# ardufocus.net
KiCad netlist of a schematic drawn in EAGLE
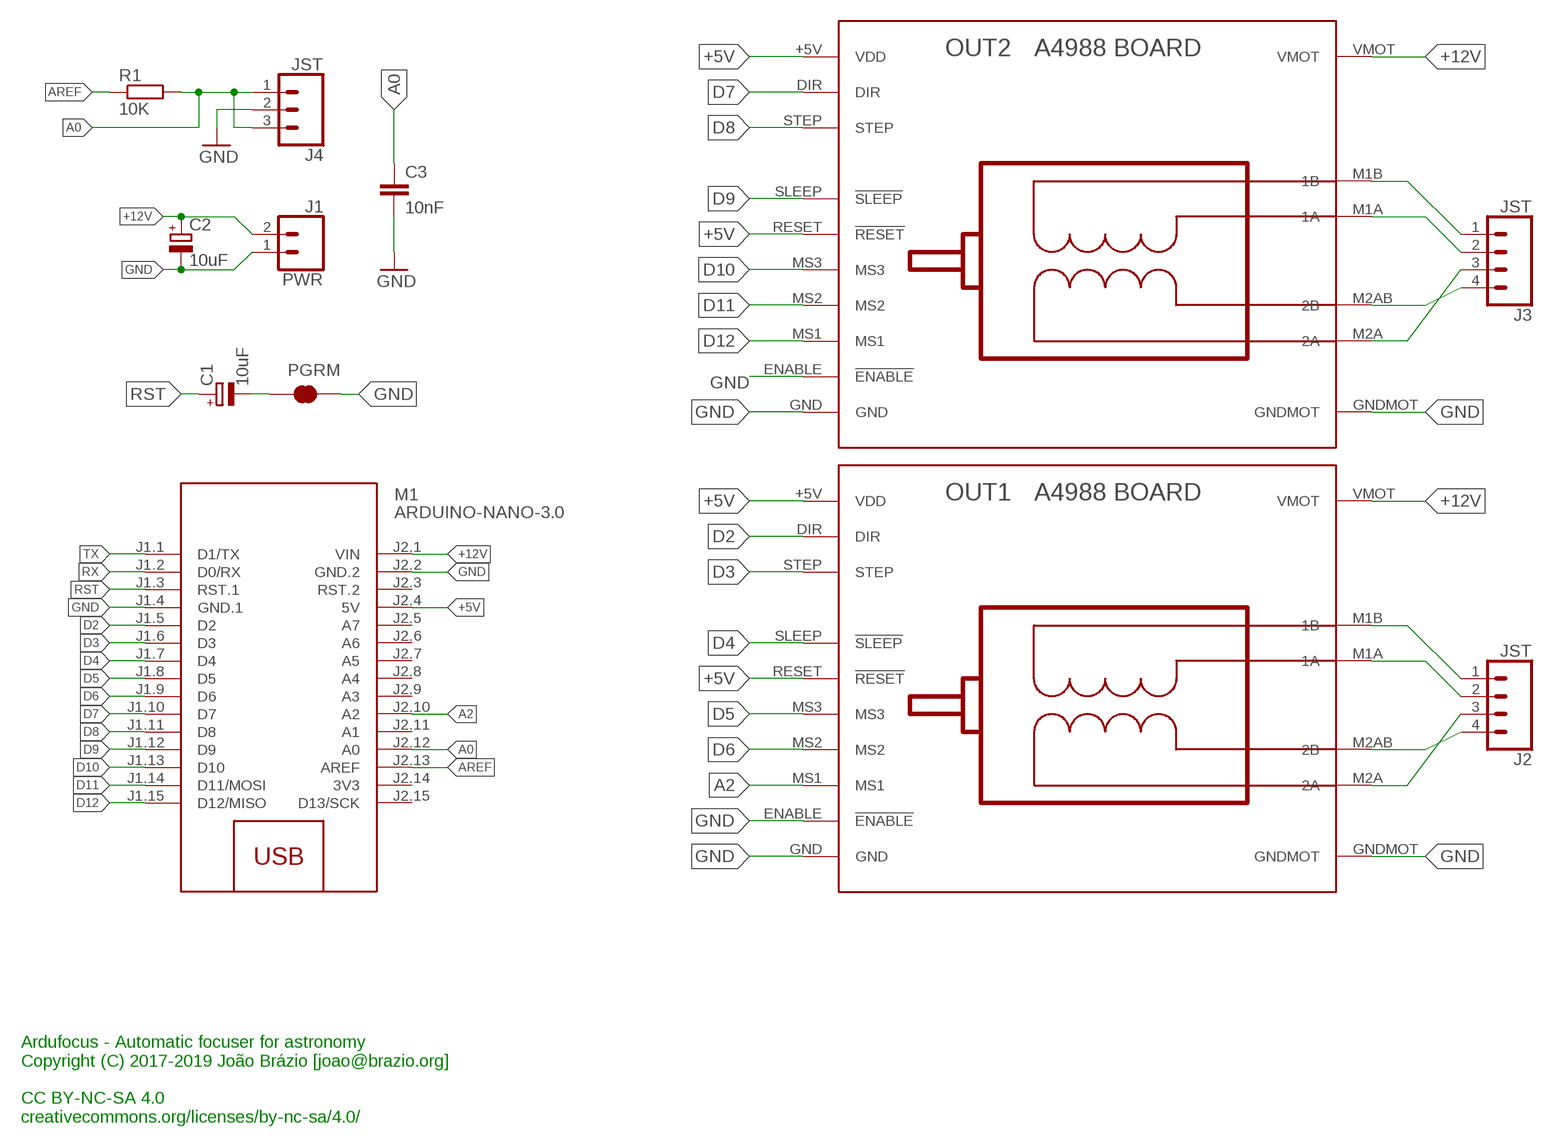
[diagram p0: schematic, sheet 1]

(export (version "E")
  (design (tool "Eeschema 10.0.6"))
  (components
    (comp (ref "C1")
      (value "10uF")
      (footprint "eagle-import:E1,8-4")
      (libsource (lib "eagle-import") (part "CPOL-EUE1.8-4"))
    )
    (comp (ref "C2")
      (value "10uF")
      (footprint "eagle-import:E2,5-6E")
      (libsource (lib "eagle-import") (part "CPOL-EUE2,5-6E"))
    )
    (comp (ref "C3")
      (value "10nF")
      (footprint "eagle-import:C3216")
      (libsource (lib "eagle-import") (part "C-EUC3216"))
    )
    (comp (ref "J1")
      (value "PWR")
      (footprint "eagle-import:SCREWTERMINAL-5MM-2")
      (libsource (lib "eagle-import") (part "CONN_025MM"))
    )
    (comp (ref "J2")
      (value "JST")
      (footprint "eagle-import:JST-4-PTH-VERT")
      (libsource (lib "eagle-import") (part "CONN_04JST-PTH-VERT"))
    )
    (comp (ref "J3")
      (value "JST")
      (footprint "eagle-import:JST-4-PTH-VERT")
      (libsource (lib "eagle-import") (part "CONN_04JST-PTH-VERT"))
    )
    (comp (ref "J4")
      (value "JST")
      (footprint "eagle-import:JST-3-PTH-VERT")
      (libsource (lib "eagle-import") (part "CONN_03JST-PTH-VERT"))
    )
    (comp (ref "M1")
      (value "ARDUINO-NANO-3.0")
      (footprint "eagle-import:ARDUINO-NANO-3.0")
      (libsource (lib "eagle-import") (part "ARDUINO-NANO-3.0"))
    )
    (comp (ref "OUT1")
      (value "BOARD_A4988")
      (footprint "eagle-import:BOARD_A4988")
      (libsource (lib "eagle-import") (part "BOARD_A4988"))
    )
    (comp (ref "OUT2")
      (value "BOARD_A4988")
      (footprint "eagle-import:BOARD_A4988")
      (libsource (lib "eagle-import") (part "BOARD_A4988"))
    )
    (comp (ref "PGRM")
      (value "JUMPER-SMT_2_NC_TRACE_SILK")
      (footprint "eagle-import:SMT-JUMPER_2_NC_TRACE_SILK")
      (libsource (lib "eagle-import") (part "JUMPER-SMT_2_NC_TRACE_SILK"))
    )
    (comp (ref "R1")
      (value "10K")
      (footprint "eagle-import:M1206")
      (libsource (lib "eagle-import") (part "R-EU_M1206"))
    )
  )
  (nets
    (net (code "1") (name "+5V") (class "Default")
      (node (ref "M1") (pin "J2.4") (pinfunction "5V_J2.4") (pintype "power_in"))
      (node (ref "OUT1") (pin "+5V") (pinfunction "VDD_+5V") (pintype "power_in"))
      (node (ref "OUT1") (pin "RESET") (pinfunction "~{RESET}_RESET") (pintype "input"))
      (node (ref "OUT2") (pin "+5V") (pinfunction "VDD_+5V") (pintype "power_in"))
      (node (ref "OUT2") (pin "RESET") (pinfunction "~{RESET}_RESET") (pintype "input"))
    )
    (net (code "2") (name "+12V") (class "Default")
      (node (ref "C2") (pin "+") (pinfunction "+_+") (pintype "passive"))
      (node (ref "J1") (pin "2") (pinfunction "2_2") (pintype "passive"))
      (node (ref "M1") (pin "J2.1") (pinfunction "VIN_J2.1") (pintype "power_in"))
      (node (ref "OUT1") (pin "VMOT") (pinfunction "VMOT_VMOT") (pintype "power_in"))
      (node (ref "OUT2") (pin "VMOT") (pinfunction "VMOT_VMOT") (pintype "power_in"))
    )
    (net (code "3") (name "/3V3") (class "Default")
      (node (ref "M1") (pin "J2.14") (pinfunction "3V3_J2.14") (pintype "power_in"))
    )
    (net (code "4") (name "A0") (class "Default")
      (node (ref "C3") (pin "1") (pinfunction "1_1") (pintype "passive"))
      (node (ref "J4") (pin "1") (pinfunction "1_1") (pintype "passive"))
      (node (ref "J4") (pin "3") (pinfunction "3_3") (pintype "passive"))
      (node (ref "M1") (pin "J2.12") (pinfunction "A0_J2.12") (pintype "bidirectional"))
      (node (ref "R1") (pin "2") (pinfunction "2_2") (pintype "passive"))
    )
    (net (code "5") (name "A2") (class "Default")
      (node (ref "M1") (pin "J2.10") (pinfunction "A2_J2.10") (pintype "bidirectional"))
      (node (ref "OUT1") (pin "MS1") (pinfunction "MS1_MS1") (pintype "input"))
    )
    (net (code "6") (name "AREF") (class "Default")
      (node (ref "M1") (pin "J2.13") (pinfunction "AREF_J2.13") (pintype "bidirectional"))
      (node (ref "R1") (pin "1") (pinfunction "1_1") (pintype "passive"))
    )
    (net (code "7") (name "D2") (class "Default")
      (node (ref "M1") (pin "J1.5") (pinfunction "D2_J1.5") (pintype "bidirectional"))
      (node (ref "OUT1") (pin "DIR") (pinfunction "DIR_DIR") (pintype "input"))
    )
    (net (code "8") (name "D3") (class "Default")
      (node (ref "M1") (pin "J1.6") (pinfunction "D3_J1.6") (pintype "bidirectional"))
      (node (ref "OUT1") (pin "STEP") (pinfunction "STEP_STEP") (pintype "input"))
    )
    (net (code "9") (name "D4") (class "Default")
      (node (ref "M1") (pin "J1.7") (pinfunction "D4_J1.7") (pintype "bidirectional"))
      (node (ref "OUT1") (pin "SLEEP") (pinfunction "~{SLEEP}_SLEEP") (pintype "input"))
    )
    (net (code "10") (name "D5") (class "Default")
      (node (ref "M1") (pin "J1.8") (pinfunction "D5_J1.8") (pintype "bidirectional"))
      (node (ref "OUT1") (pin "MS3") (pinfunction "MS3_MS3") (pintype "input"))
    )
    (net (code "11") (name "D6") (class "Default")
      (node (ref "M1") (pin "J1.9") (pinfunction "D6_J1.9") (pintype "bidirectional"))
      (node (ref "OUT1") (pin "MS2") (pinfunction "MS2_MS2") (pintype "input"))
    )
    (net (code "12") (name "D7") (class "Default")
      (node (ref "M1") (pin "J1.10") (pinfunction "D7_J1.10") (pintype "bidirectional"))
      (node (ref "OUT2") (pin "DIR") (pinfunction "DIR_DIR") (pintype "input"))
    )
    (net (code "13") (name "D8") (class "Default")
      (node (ref "M1") (pin "J1.11") (pinfunction "D8_J1.11") (pintype "bidirectional"))
      (node (ref "OUT2") (pin "STEP") (pinfunction "STEP_STEP") (pintype "input"))
    )
    (net (code "14") (name "D9") (class "Default")
      (node (ref "M1") (pin "J1.12") (pinfunction "D9_J1.12") (pintype "bidirectional"))
      (node (ref "OUT2") (pin "SLEEP") (pinfunction "~{SLEEP}_SLEEP") (pintype "input"))
    )
    (net (code "15") (name "D10") (class "Default")
      (node (ref "M1") (pin "J1.13") (pinfunction "D10_J1.13") (pintype "bidirectional"))
      (node (ref "OUT2") (pin "MS3") (pinfunction "MS3_MS3") (pintype "input"))
    )
    (net (code "16") (name "D11") (class "Default")
      (node (ref "M1") (pin "J1.14") (pinfunction "D11/MOSI_J1.14") (pintype "bidirectional"))
      (node (ref "OUT2") (pin "MS2") (pinfunction "MS2_MS2") (pintype "input"))
    )
    (net (code "17") (name "D12") (class "Default")
      (node (ref "M1") (pin "J1.15") (pinfunction "D12/MISO_J1.15") (pintype "bidirectional"))
      (node (ref "OUT2") (pin "MS1") (pinfunction "MS1_MS1") (pintype "input"))
    )
    (net (code "18") (name "GND") (class "Default")
      (node (ref "C2") (pin "-") (pinfunction "-_-") (pintype "passive"))
      (node (ref "C3") (pin "2") (pinfunction "2_2") (pintype "passive"))
      (node (ref "J1") (pin "1") (pinfunction "1_1") (pintype "passive"))
      (node (ref "J4") (pin "2") (pinfunction "2_2") (pintype "passive"))
      (node (ref "M1") (pin "J1.4") (pinfunction "GND.1_J1.4") (pintype "power_in"))
      (node (ref "M1") (pin "J2.2") (pinfunction "GND.2_J2.2") (pintype "power_in"))
      (node (ref "OUT1") (pin "ENABLE") (pinfunction "~{ENABLE}_ENABLE") (pintype "input"))
      (node (ref "OUT1") (pin "GND") (pinfunction "GND_GND") (pintype "power_in"))
      (node (ref "OUT1") (pin "GNDMOT") (pinfunction "GNDMOT_GNDMOT") (pintype "power_in"))
      (node (ref "OUT2") (pin "ENABLE") (pinfunction "~{ENABLE}_ENABLE") (pintype "input"))
      (node (ref "OUT2") (pin "GND") (pinfunction "GND_GND") (pintype "power_in"))
      (node (ref "OUT2") (pin "GNDMOT") (pinfunction "GNDMOT_GNDMOT") (pintype "power_in"))
      (node (ref "PGRM") (pin "2") (pinfunction "2_2") (pintype "passive"))
    )
    (net (code "19") (name "Net-(C1-Pad-)") (class "Default")
      (node (ref "C1") (pin "-") (pinfunction "-_-") (pintype "passive"))
      (node (ref "PGRM") (pin "1") (pinfunction "1_1") (pintype "passive"))
    )
    (net (code "20") (name "Net-(OUT1-1A)") (class "Default")
      (node (ref "J2") (pin "2") (pinfunction "2_2") (pintype "passive"))
      (node (ref "OUT1") (pin "M1A") (pinfunction "1A_M1A") (pintype "output"))
    )
    (net (code "21") (name "Net-(OUT1-1B)") (class "Default")
      (node (ref "J2") (pin "1") (pinfunction "1_1") (pintype "passive"))
      (node (ref "OUT1") (pin "M1B") (pinfunction "1B_M1B") (pintype "output"))
    )
    (net (code "22") (name "Net-(OUT1-2A)") (class "Default")
      (node (ref "J2") (pin "3") (pinfunction "3_3") (pintype "passive"))
      (node (ref "OUT1") (pin "M2A") (pinfunction "2A_M2A") (pintype "output"))
    )
    (net (code "23") (name "Net-(OUT1-2B)") (class "Default")
      (node (ref "J2") (pin "4") (pinfunction "4_4") (pintype "passive"))
      (node (ref "OUT1") (pin "M2AB") (pinfunction "2B_M2AB") (pintype "output"))
    )
    (net (code "24") (name "Net-(OUT2-1A)") (class "Default")
      (node (ref "J3") (pin "2") (pinfunction "2_2") (pintype "passive"))
      (node (ref "OUT2") (pin "M1A") (pinfunction "1A_M1A") (pintype "output"))
    )
    (net (code "25") (name "Net-(OUT2-1B)") (class "Default")
      (node (ref "J3") (pin "1") (pinfunction "1_1") (pintype "passive"))
      (node (ref "OUT2") (pin "M1B") (pinfunction "1B_M1B") (pintype "output"))
    )
    (net (code "26") (name "Net-(OUT2-2A)") (class "Default")
      (node (ref "J3") (pin "3") (pinfunction "3_3") (pintype "passive"))
      (node (ref "OUT2") (pin "M2A") (pinfunction "2A_M2A") (pintype "output"))
    )
    (net (code "27") (name "Net-(OUT2-2B)") (class "Default")
      (node (ref "J3") (pin "4") (pinfunction "4_4") (pintype "passive"))
      (node (ref "OUT2") (pin "M2AB") (pinfunction "2B_M2AB") (pintype "output"))
    )
    (net (code "28") (name "RST") (class "Default")
      (node (ref "C1") (pin "+") (pinfunction "+_+") (pintype "passive"))
      (node (ref "M1") (pin "J1.3") (pinfunction "RST.1_J1.3") (pintype "bidirectional"))
    )
    (net (code "29") (name "RX") (class "Default")
      (node (ref "M1") (pin "J1.2") (pinfunction "D0/RX_J1.2") (pintype "bidirectional"))
    )
    (net (code "30") (name "TX") (class "Default")
      (node (ref "M1") (pin "J1.1") (pinfunction "D1/TX_J1.1") (pintype "bidirectional"))
    )
    (net (code "31") (name "unconnected-(M1-A1-PadJ2.11)") (class "Default")
      (node (ref "M1") (pin "J2.11") (pinfunction "A1_J2.11") (pintype "bidirectional"))
    )
    (net (code "32") (name "unconnected-(M1-A3-PadJ2.9)") (class "Default")
      (node (ref "M1") (pin "J2.9") (pinfunction "A3_J2.9") (pintype "bidirectional"))
    )
    (net (code "33") (name "unconnected-(M1-A4-PadJ2.8)") (class "Default")
      (node (ref "M1") (pin "J2.8") (pinfunction "A4_J2.8") (pintype "bidirectional"))
    )
    (net (code "34") (name "unconnected-(M1-A5-PadJ2.7)") (class "Default")
      (node (ref "M1") (pin "J2.7") (pinfunction "A5_J2.7") (pintype "bidirectional"))
    )
    (net (code "35") (name "unconnected-(M1-A6-PadJ2.6)") (class "Default")
      (node (ref "M1") (pin "J2.6") (pinfunction "A6_J2.6") (pintype "bidirectional"))
    )
    (net (code "36") (name "unconnected-(M1-A7-PadJ2.5)") (class "Default")
      (node (ref "M1") (pin "J2.5") (pinfunction "A7_J2.5") (pintype "bidirectional"))
    )
    (net (code "37") (name "unconnected-(M1-D13{slash}SCK-PadJ2.15)") (class "Default")
      (node (ref "M1") (pin "J2.15") (pinfunction "D13/SCK_J2.15") (pintype "bidirectional"))
    )
    (net (code "38") (name "unconnected-(M1-RST.2-PadJ2.3)") (class "Default")
      (node (ref "M1") (pin "J2.3") (pinfunction "RST.2_J2.3") (pintype "bidirectional"))
    )
  )
)
